# gbg_base_reva.net
KiCad netlist of a schematic drawn in EAGLE
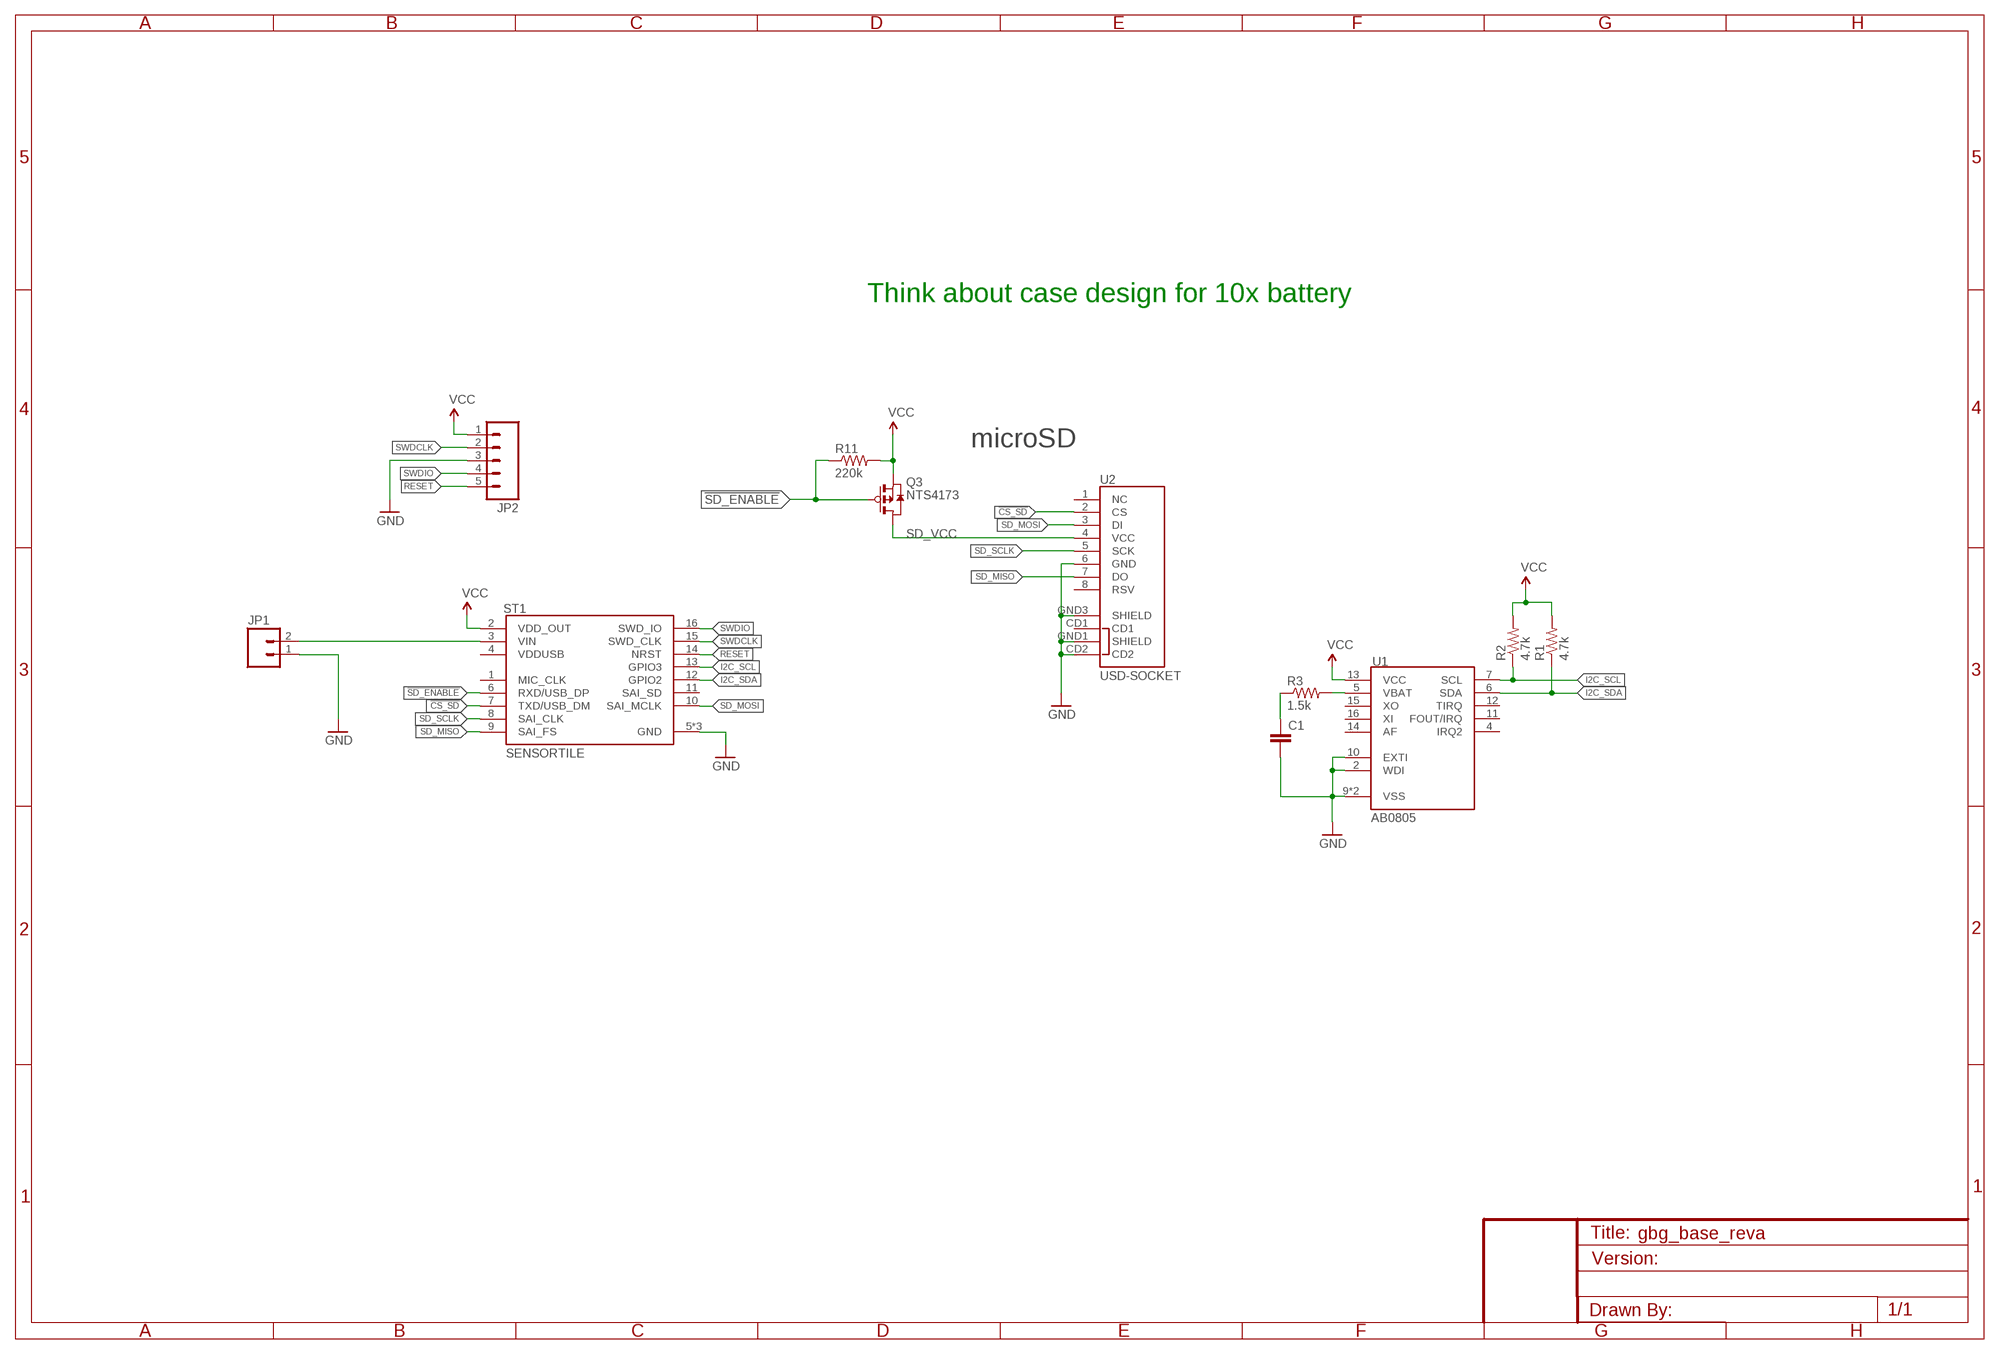
[diagram p0: schematic, sheet 1]

(export (version "E")
  (design (tool "Eeschema 10.0.6"))
  (components
    (comp (ref "C1")
      (value "CAP1210")
      (footprint "eagle-import:1210")
      (libsource (lib "eagle-import") (part "CAP1210"))
    )
    (comp (ref "JP1")
      (value "M02PTH")
      (footprint "eagle-import:1X02")
      (libsource (lib "eagle-import") (part "M02PTH"))
    )
    (comp (ref "JP2")
      (value "M05LOCK")
      (footprint "eagle-import:1X05_LOCK")
      (libsource (lib "eagle-import") (part "M05LOCK"))
    )
    (comp (ref "Q3")
      (value "NTS4173")
      (footprint "eagle-import:SC-70-3")
      (libsource (lib "eagle-import") (part "NTS4173"))
    )
    (comp (ref "R1")
      (value "4.7k")
      (footprint "eagle-import:0603-RES")
      (libsource (lib "eagle-import") (part "RESISTOR0603"))
    )
    (comp (ref "R2")
      (value "4.7k")
      (footprint "eagle-import:0603-RES")
      (libsource (lib "eagle-import") (part "RESISTOR0603"))
    )
    (comp (ref "R3")
      (value "1.5k")
      (footprint "eagle-import:0603-RES")
      (libsource (lib "eagle-import") (part "RESISTOR0603"))
    )
    (comp (ref "R11")
      (value "220k")
      (footprint "eagle-import:0603")
      (libsource (lib "eagle-import") (part "R-EU0603"))
    )
    (comp (ref "ST1")
      (value "SENSORTILE")
      (footprint "eagle-import:SENSORTILE")
      (libsource (lib "eagle-import") (part "SENSORTILE"))
    )
    (comp (ref "U1")
      (value "AB0805")
      (footprint "eagle-import:QFN16")
      (libsource (lib "eagle-import") (part "AB0805"))
    )
    (comp (ref "U2")
      (value "USD-SOCKET")
      (footprint "eagle-import:MICROSD_1_1")
      (libsource (lib "eagle-import") (part "USD-SOCKET"))
    )
  )
  (nets
    (net (code "1") (name "/SD_VCC") (class "Default")
      (node (ref "Q3") (pin "P3") (pinfunction "D_P3") (pintype "passive"))
      (node (ref "U2") (pin "4") (pinfunction "VCC_4") (pintype "bidirectional"))
    )
    (net (code "2") (name "/~{CS_SD}") (class "Default")
      (node (ref "ST1") (pin "7") (pinfunction "TXD/USB_DM_7") (pintype "bidirectional"))
      (node (ref "U2") (pin "2") (pinfunction "CS_2") (pintype "bidirectional"))
    )
    (net (code "3") (name "/~{SD_ENABLE}") (class "Default")
      (node (ref "Q3") (pin "P1") (pinfunction "G_P1") (pintype "passive"))
      (node (ref "R11") (pin "1") (pinfunction "1_1") (pintype "passive"))
      (node (ref "ST1") (pin "6") (pinfunction "RXD/USB_DP_6") (pintype "bidirectional"))
    )
    (net (code "4") (name "GND") (class "Default")
      (node (ref "C1") (pin "2") (pinfunction "2_2") (pintype "passive"))
      (node (ref "JP1") (pin "1") (pinfunction "1_1") (pintype "passive"))
      (node (ref "JP2") (pin "3") (pinfunction "3_3") (pintype "passive"))
      (node (ref "ST1") (pin "17") (pinfunction "GND_17") (pintype "bidirectional"))
      (node (ref "ST1") (pin "18") (pinfunction "GND_18") (pintype "bidirectional"))
      (node (ref "ST1") (pin "5") (pinfunction "GND_5") (pintype "bidirectional"))
      (node (ref "U1") (pin "10") (pinfunction "EXTI_10") (pintype "bidirectional"))
      (node (ref "U1") (pin "2") (pinfunction "WDI_2") (pintype "bidirectional"))
      (node (ref "U1") (pin "9") (pinfunction "VSS_9") (pintype "bidirectional"))
      (node (ref "U1") (pin "TH") (pinfunction "VSS_TH") (pintype "bidirectional"))
      (node (ref "U2") (pin "6") (pinfunction "GND_6") (pintype "bidirectional"))
      (node (ref "U2") (pin "CD2") (pinfunction "CD2_CD2") (pintype "bidirectional"))
      (node (ref "U2") (pin "GND1") (pinfunction "SHIELD_GND1") (pintype "bidirectional"))
      (node (ref "U2") (pin "GND3") (pinfunction "SHIELD_GND3") (pintype "bidirectional"))
    )
    (net (code "5") (name "I2C_SCL") (class "Default")
      (node (ref "R2") (pin "1") (pinfunction "1_1") (pintype "passive"))
      (node (ref "ST1") (pin "13") (pinfunction "GPIO3_13") (pintype "bidirectional"))
      (node (ref "U1") (pin "7") (pinfunction "SCL_7") (pintype "bidirectional"))
    )
    (net (code "6") (name "I2C_SDA") (class "Default")
      (node (ref "R1") (pin "1") (pinfunction "1_1") (pintype "passive"))
      (node (ref "ST1") (pin "12") (pinfunction "GPIO2_12") (pintype "bidirectional"))
      (node (ref "U1") (pin "6") (pinfunction "SDA_6") (pintype "bidirectional"))
    )
    (net (code "7") (name "Net-(C1-Pad1)") (class "Default")
      (node (ref "C1") (pin "1") (pinfunction "1_1") (pintype "passive"))
      (node (ref "R3") (pin "1") (pinfunction "1_1") (pintype "passive"))
    )
    (net (code "8") (name "Net-(ST1-VIN)") (class "Default")
      (node (ref "JP1") (pin "2") (pinfunction "2_2") (pintype "passive"))
      (node (ref "ST1") (pin "3") (pinfunction "VIN_3") (pintype "bidirectional"))
    )
    (net (code "9") (name "Net-(U1-VBAT)") (class "Default")
      (node (ref "R3") (pin "2") (pinfunction "2_2") (pintype "passive"))
      (node (ref "U1") (pin "5") (pinfunction "VBAT_5") (pintype "bidirectional"))
    )
    (net (code "10") (name "RESET") (class "Default")
      (node (ref "JP2") (pin "5") (pinfunction "5_5") (pintype "passive"))
      (node (ref "ST1") (pin "14") (pinfunction "NRST_14") (pintype "bidirectional"))
    )
    (net (code "11") (name "SD_MISO") (class "Default")
      (node (ref "ST1") (pin "9") (pinfunction "SAI_FS_9") (pintype "bidirectional"))
      (node (ref "U2") (pin "7") (pinfunction "DO_7") (pintype "bidirectional"))
    )
    (net (code "12") (name "SD_MOSI") (class "Default")
      (node (ref "ST1") (pin "10") (pinfunction "SAI_MCLK_10") (pintype "bidirectional"))
      (node (ref "U2") (pin "3") (pinfunction "DI_3") (pintype "bidirectional"))
    )
    (net (code "13") (name "SD_SCLK") (class "Default")
      (node (ref "ST1") (pin "8") (pinfunction "SAI_CLK_8") (pintype "bidirectional"))
      (node (ref "U2") (pin "5") (pinfunction "SCK_5") (pintype "bidirectional"))
    )
    (net (code "14") (name "SWDCLK") (class "Default")
      (node (ref "JP2") (pin "2") (pinfunction "2_2") (pintype "passive"))
      (node (ref "ST1") (pin "15") (pinfunction "SWD_CLK_15") (pintype "bidirectional"))
    )
    (net (code "15") (name "SWDIO") (class "Default")
      (node (ref "JP2") (pin "4") (pinfunction "4_4") (pintype "passive"))
      (node (ref "ST1") (pin "16") (pinfunction "SWD_IO_16") (pintype "bidirectional"))
    )
    (net (code "16") (name "VCC") (class "Default")
      (node (ref "JP2") (pin "1") (pinfunction "1_1") (pintype "passive"))
      (node (ref "Q3") (pin "P2") (pinfunction "S_P2") (pintype "passive"))
      (node (ref "R1") (pin "2") (pinfunction "2_2") (pintype "passive"))
      (node (ref "R11") (pin "2") (pinfunction "2_2") (pintype "passive"))
      (node (ref "R2") (pin "2") (pinfunction "2_2") (pintype "passive"))
      (node (ref "ST1") (pin "2") (pinfunction "VDD_OUT_2") (pintype "bidirectional"))
      (node (ref "U1") (pin "13") (pinfunction "VCC_13") (pintype "bidirectional"))
    )
    (net (code "17") (name "unconnected-(ST1-MIC_CLK-Pad1)") (class "Default")
      (node (ref "ST1") (pin "1") (pinfunction "MIC_CLK_1") (pintype "bidirectional"))
    )
    (net (code "18") (name "unconnected-(ST1-SAI_SD-Pad11)") (class "Default")
      (node (ref "ST1") (pin "11") (pinfunction "SAI_SD_11") (pintype "bidirectional"))
    )
    (net (code "19") (name "unconnected-(ST1-VDDUSB-Pad4)") (class "Default")
      (node (ref "ST1") (pin "4") (pinfunction "VDDUSB_4") (pintype "bidirectional"))
    )
    (net (code "20") (name "unconnected-(U1-AF-Pad14)") (class "Default")
      (node (ref "U1") (pin "14") (pinfunction "AF_14") (pintype "bidirectional"))
    )
    (net (code "21") (name "unconnected-(U1-FOUT{slash}IRQ-Pad11)") (class "Default")
      (node (ref "U1") (pin "11") (pinfunction "FOUT/IRQ_11") (pintype "bidirectional"))
    )
    (net (code "22") (name "unconnected-(U1-IRQ2-Pad4)") (class "Default")
      (node (ref "U1") (pin "4") (pinfunction "IRQ2_4") (pintype "bidirectional"))
    )
    (net (code "23") (name "unconnected-(U1-TIRQ-Pad12)") (class "Default")
      (node (ref "U1") (pin "12") (pinfunction "TIRQ_12") (pintype "bidirectional"))
    )
    (net (code "24") (name "unconnected-(U1-XI-Pad16)") (class "Default")
      (node (ref "U1") (pin "16") (pinfunction "XI_16") (pintype "bidirectional"))
    )
    (net (code "25") (name "unconnected-(U1-XO-Pad15)") (class "Default")
      (node (ref "U1") (pin "15") (pinfunction "XO_15") (pintype "bidirectional"))
    )
    (net (code "26") (name "unconnected-(U2-NC-Pad1)") (class "Default")
      (node (ref "U2") (pin "1") (pinfunction "NC_1") (pintype "bidirectional"))
    )
    (net (code "27") (name "unconnected-(U2-PadCD1)") (class "Default")
      (node (ref "U2") (pin "CD1") (pinfunction "CD1_CD1") (pintype "bidirectional"))
    )
    (net (code "28") (name "unconnected-(U2-RSV-Pad8)") (class "Default")
      (node (ref "U2") (pin "8") (pinfunction "RSV_8") (pintype "bidirectional"))
    )
  )
)
